# Z.net
KiCad netlist of a schematic drawn in Altium Designer
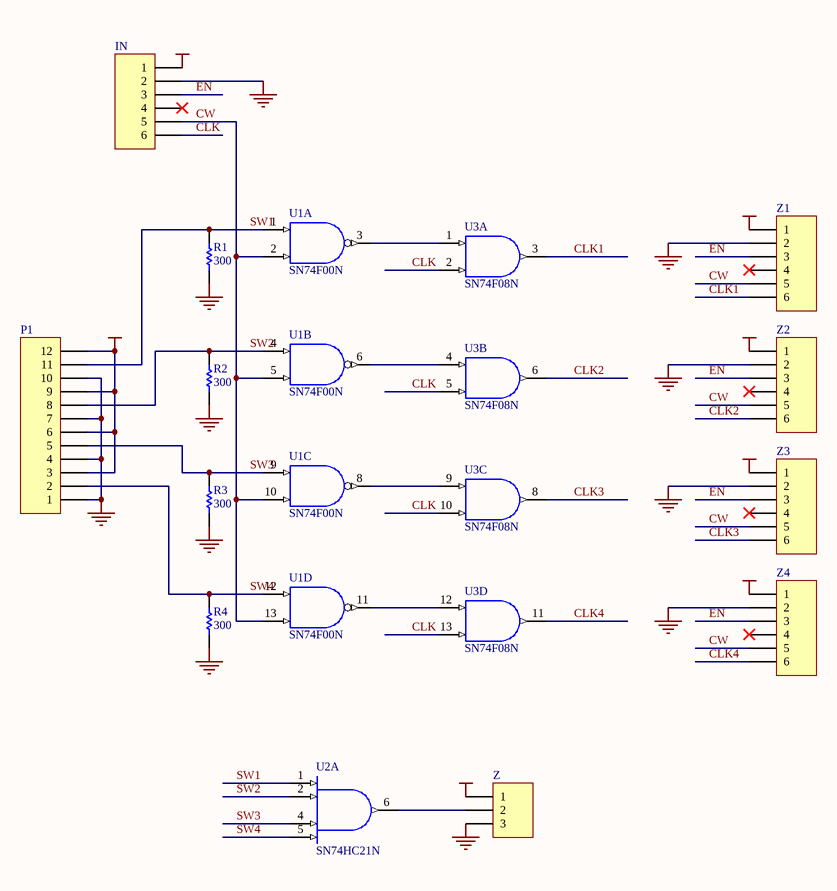
[diagram p0: 校正Z軸電路.SchDoc]

(export (version "E")
  (design (tool "Eeschema 10.0.6"))
  (components
    (comp (ref "IN")
      (value "Header 6")
      (footprint "2.54mm 6pin")
      (description "Header, 6-Pin")
      (fields (field (name "PUBLISHER") "Altium Limited"))
      (libsource (lib "") (part "Header 6_1"))
    )
    (comp (ref "P1")
      (value "Header 12")
      (footprint "2.5mm 12pin")
      (description "Header, 12-Pin")
      (fields (field (name "PUBLISHER") "Altium Limited"))
      (libsource (lib "Miscellaneous Connectors") (part "Header 12"))
    )
    (comp (ref "R1")
      (value "300")
      (footprint "AXIAL-0.3")
      (description "Resistor")
      (fields (field (name "Comment") "Res1") (field (name "PUBLISHER") "Altium Limited"))
      (libsource (lib "Miscellaneous Devices") (part "Res1"))
    )
    (comp (ref "R2")
      (value "300")
      (footprint "AXIAL-0.3")
      (description "Resistor")
      (fields (field (name "Comment") "Res1") (field (name "PUBLISHER") "Altium Limited"))
      (libsource (lib "Miscellaneous Devices") (part "Res1"))
    )
    (comp (ref "R3")
      (value "300")
      (footprint "AXIAL-0.3")
      (description "Resistor")
      (fields (field (name "Comment") "Res1") (field (name "PUBLISHER") "Altium Limited"))
      (libsource (lib "Miscellaneous Devices") (part "Res1"))
    )
    (comp (ref "R4")
      (value "300")
      (footprint "AXIAL-0.3")
      (description "Resistor")
      (fields (field (name "Comment") "Res1") (field (name "PUBLISHER") "Altium Limited"))
      (libsource (lib "Miscellaneous Devices") (part "Res1"))
    )
    (comp (ref "U1")
      (value "SN74F00N")
      (footprint "N014")
      (description "Quadruple 2-Input Positive-NAND Gate")
      (fields (field (name "PUBLISHER") "Altium Limited"))
      (libsource (lib "TI Logic Gate 2") (part "SN74F00N"))
    )
    (comp (ref "U2")
      (value "SN74HC21N")
      (footprint "N014")
      (description "Dual 4-Input Positive-AND Gate")
      (fields (field (name "PUBLISHER") "Altium Limited"))
      (libsource (lib "TI Logic Gate 2") (part "SN74HC21N"))
    )
    (comp (ref "U3")
      (value "SN74F08N")
      (footprint "N014")
      (description "Quadruple 2-Input Positive-AND Gate")
      (fields (field (name "PUBLISHER") "Altium Limited"))
      (libsource (lib "TI Logic Gate 2") (part "SN74F08N"))
    )
    (comp (ref "Z")
      (value "Header 3")
      (footprint "2.54mm 3pin")
      (description "Header, 3-Pin")
      (fields (field (name "PUBLISHER") "Altium Limited"))
      (libsource (lib "Miscellaneous Connectors") (part "Header 3"))
    )
    (comp (ref "Z1")
      (value "Header 6")
      (footprint "2.54mm 6pin")
      (description "Header, 6-Pin")
      (fields (field (name "PUBLISHER") "Altium Limited"))
      (libsource (lib "Miscellaneous Connectors") (part "Header 6"))
    )
    (comp (ref "Z2")
      (value "Header 6")
      (footprint "2.54mm 6pin")
      (description "Header, 6-Pin")
      (fields (field (name "PUBLISHER") "Altium Limited"))
      (libsource (lib "Miscellaneous Connectors") (part "Header 6"))
    )
    (comp (ref "Z3")
      (value "Header 6")
      (footprint "2.54mm 6pin")
      (description "Header, 6-Pin")
      (fields (field (name "PUBLISHER") "Altium Limited"))
      (libsource (lib "Miscellaneous Connectors") (part "Header 6"))
    )
    (comp (ref "Z4")
      (value "Header 6")
      (footprint "2.54mm 6pin")
      (description "Header, 6-Pin")
      (fields (field (name "PUBLISHER") "Altium Limited"))
      (libsource (lib "Miscellaneous Connectors") (part "Header 6"))
    )
  )
  (nets
    (net (code "1") (name "/CLK") (class "Default")
      (node (ref "IN") (pin "6") (pinfunction "6_6") (pintype "passive"))
      (node (ref "U3") (pin "10") (pinfunction "B_10") (pintype "input"))
      (node (ref "U3") (pin "13") (pinfunction "B_13") (pintype "input"))
      (node (ref "U3") (pin "2") (pinfunction "B_2") (pintype "input"))
      (node (ref "U3") (pin "5") (pinfunction "B_5") (pintype "input"))
    )
    (net (code "2") (name "/CLK1") (class "Default")
      (node (ref "U3") (pin "3") (pinfunction "Y_3") (pintype "output"))
      (node (ref "Z1") (pin "6") (pinfunction "6_6") (pintype "passive"))
    )
    (net (code "3") (name "/CLK2") (class "Default")
      (node (ref "U3") (pin "6") (pinfunction "Y_6") (pintype "output"))
      (node (ref "Z2") (pin "6") (pinfunction "6_6") (pintype "passive"))
    )
    (net (code "4") (name "/CLK3") (class "Default")
      (node (ref "U3") (pin "8") (pinfunction "Y_8") (pintype "output"))
      (node (ref "Z3") (pin "6") (pinfunction "6_6") (pintype "passive"))
    )
    (net (code "5") (name "/CLK4") (class "Default")
      (node (ref "U3") (pin "11") (pinfunction "Y_11") (pintype "output"))
      (node (ref "Z4") (pin "6") (pinfunction "6_6") (pintype "passive"))
    )
    (net (code "6") (name "/CW") (class "Default")
      (node (ref "IN") (pin "5") (pinfunction "5_5") (pintype "passive"))
      (node (ref "U1") (pin "10") (pinfunction "B_10") (pintype "input"))
      (node (ref "U1") (pin "13") (pinfunction "B_13") (pintype "input"))
      (node (ref "U1") (pin "2") (pinfunction "B_2") (pintype "input"))
      (node (ref "U1") (pin "5") (pinfunction "B_5") (pintype "input"))
      (node (ref "Z1") (pin "5") (pinfunction "5_5") (pintype "passive"))
      (node (ref "Z2") (pin "5") (pinfunction "5_5") (pintype "passive"))
      (node (ref "Z3") (pin "5") (pinfunction "5_5") (pintype "passive"))
      (node (ref "Z4") (pin "5") (pinfunction "5_5") (pintype "passive"))
    )
    (net (code "7") (name "/EN") (class "Default")
      (node (ref "IN") (pin "3") (pinfunction "3_3") (pintype "passive"))
      (node (ref "Z1") (pin "3") (pinfunction "3_3") (pintype "passive"))
      (node (ref "Z2") (pin "3") (pinfunction "3_3") (pintype "passive"))
      (node (ref "Z3") (pin "3") (pinfunction "3_3") (pintype "passive"))
      (node (ref "Z4") (pin "3") (pinfunction "3_3") (pintype "passive"))
    )
    (net (code "8") (name "/SW1") (class "Default")
      (node (ref "P1") (pin "11") (pinfunction "11_11") (pintype "passive"))
      (node (ref "R1") (pin "2") (pinfunction "2_2") (pintype "passive"))
      (node (ref "U1") (pin "1") (pinfunction "A_1") (pintype "input"))
      (node (ref "U2") (pin "1") (pinfunction "A_1") (pintype "input"))
    )
    (net (code "9") (name "/SW2") (class "Default")
      (node (ref "P1") (pin "8") (pinfunction "8_8") (pintype "passive"))
      (node (ref "R2") (pin "2") (pinfunction "2_2") (pintype "passive"))
      (node (ref "U1") (pin "4") (pinfunction "A_4") (pintype "input"))
      (node (ref "U2") (pin "2") (pinfunction "B_2") (pintype "input"))
    )
    (net (code "10") (name "/SW3") (class "Default")
      (node (ref "P1") (pin "5") (pinfunction "5_5") (pintype "passive"))
      (node (ref "R3") (pin "2") (pinfunction "2_2") (pintype "passive"))
      (node (ref "U1") (pin "9") (pinfunction "A_9") (pintype "input"))
      (node (ref "U2") (pin "4") (pinfunction "C_4") (pintype "input"))
    )
    (net (code "11") (name "/SW4") (class "Default")
      (node (ref "P1") (pin "2") (pinfunction "2_2") (pintype "passive"))
      (node (ref "R4") (pin "2") (pinfunction "2_2") (pintype "passive"))
      (node (ref "U1") (pin "12") (pinfunction "A_12") (pintype "input"))
      (node (ref "U2") (pin "5") (pinfunction "D_5") (pintype "input"))
    )
    (net (code "12") (name "GND") (class "Default")
      (node (ref "IN") (pin "2") (pinfunction "2_2") (pintype "passive"))
      (node (ref "P1") (pin "1") (pinfunction "1_1") (pintype "passive"))
      (node (ref "P1") (pin "10") (pinfunction "10_10") (pintype "passive"))
      (node (ref "P1") (pin "4") (pinfunction "4_4") (pintype "passive"))
      (node (ref "P1") (pin "7") (pinfunction "7_7") (pintype "passive"))
      (node (ref "R1") (pin "1") (pinfunction "1_1") (pintype "passive"))
      (node (ref "R2") (pin "1") (pinfunction "1_1") (pintype "passive"))
      (node (ref "R3") (pin "1") (pinfunction "1_1") (pintype "passive"))
      (node (ref "R4") (pin "1") (pinfunction "1_1") (pintype "passive"))
      (node (ref "U1") (pin "7") (pinfunction "GND_7") (pintype "power_in"))
      (node (ref "U2") (pin "7") (pinfunction "GND_7") (pintype "power_in"))
      (node (ref "U3") (pin "7") (pinfunction "GND_7") (pintype "power_in"))
      (node (ref "Z") (pin "3") (pinfunction "3_3") (pintype "passive"))
      (node (ref "Z1") (pin "2") (pinfunction "2_2") (pintype "passive"))
      (node (ref "Z2") (pin "2") (pinfunction "2_2") (pintype "passive"))
      (node (ref "Z3") (pin "2") (pinfunction "2_2") (pintype "passive"))
      (node (ref "Z4") (pin "2") (pinfunction "2_2") (pintype "passive"))
    )
    (net (code "13") (name "Net-(U1A-Y)") (class "Default")
      (node (ref "U1") (pin "3") (pinfunction "Y_3") (pintype "output"))
      (node (ref "U3") (pin "1") (pinfunction "A_1") (pintype "input"))
    )
    (net (code "14") (name "Net-(U1B-Y)") (class "Default")
      (node (ref "U1") (pin "6") (pinfunction "Y_6") (pintype "output"))
      (node (ref "U3") (pin "4") (pinfunction "A_4") (pintype "input"))
    )
    (net (code "15") (name "Net-(U1C-Y)") (class "Default")
      (node (ref "U1") (pin "8") (pinfunction "Y_8") (pintype "output"))
      (node (ref "U3") (pin "9") (pinfunction "A_9") (pintype "input"))
    )
    (net (code "16") (name "Net-(U1D-Y)") (class "Default")
      (node (ref "U1") (pin "11") (pinfunction "Y_11") (pintype "output"))
      (node (ref "U3") (pin "12") (pinfunction "A_12") (pintype "input"))
    )
    (net (code "17") (name "Net-(U2A-Y)") (class "Default")
      (node (ref "U2") (pin "6") (pinfunction "Y_6") (pintype "output"))
      (node (ref "Z") (pin "2") (pinfunction "2_2") (pintype "passive"))
    )
    (net (code "18") (name "VCC") (class "Default")
      (node (ref "IN") (pin "1") (pinfunction "1_1") (pintype "passive"))
      (node (ref "P1") (pin "12") (pinfunction "12_12") (pintype "passive"))
      (node (ref "P1") (pin "3") (pinfunction "3_3") (pintype "passive"))
      (node (ref "P1") (pin "6") (pinfunction "6_6") (pintype "passive"))
      (node (ref "P1") (pin "9") (pinfunction "9_9") (pintype "passive"))
      (node (ref "U1") (pin "14") (pinfunction "VCC_14") (pintype "power_in"))
      (node (ref "U2") (pin "14") (pinfunction "VCC_14") (pintype "power_in"))
      (node (ref "U3") (pin "14") (pinfunction "VCC_14") (pintype "power_in"))
      (node (ref "Z") (pin "1") (pinfunction "1_1") (pintype "passive"))
      (node (ref "Z1") (pin "1") (pinfunction "1_1") (pintype "passive"))
      (node (ref "Z2") (pin "1") (pinfunction "1_1") (pintype "passive"))
      (node (ref "Z3") (pin "1") (pinfunction "1_1") (pintype "passive"))
      (node (ref "Z4") (pin "1") (pinfunction "1_1") (pintype "passive"))
    )
    (net (code "19") (name "unconnected-(IN-Pad4)") (class "Default")
      (node (ref "IN") (pin "4") (pinfunction "4_4") (pintype "passive+no_connect"))
    )
    (net (code "20") (name "unconnected-(Z1-Pad4)") (class "Default")
      (node (ref "Z1") (pin "4") (pinfunction "4_4") (pintype "passive+no_connect"))
    )
    (net (code "21") (name "unconnected-(Z2-Pad4)") (class "Default")
      (node (ref "Z2") (pin "4") (pinfunction "4_4") (pintype "passive+no_connect"))
    )
    (net (code "22") (name "unconnected-(Z3-Pad4)") (class "Default")
      (node (ref "Z3") (pin "4") (pinfunction "4_4") (pintype "passive+no_connect"))
    )
    (net (code "23") (name "unconnected-(Z4-Pad4)") (class "Default")
      (node (ref "Z4") (pin "4") (pinfunction "4_4") (pintype "passive+no_connect"))
    )
  )
)
